# scs.net
KiCad netlist of a schematic drawn in EAGLE
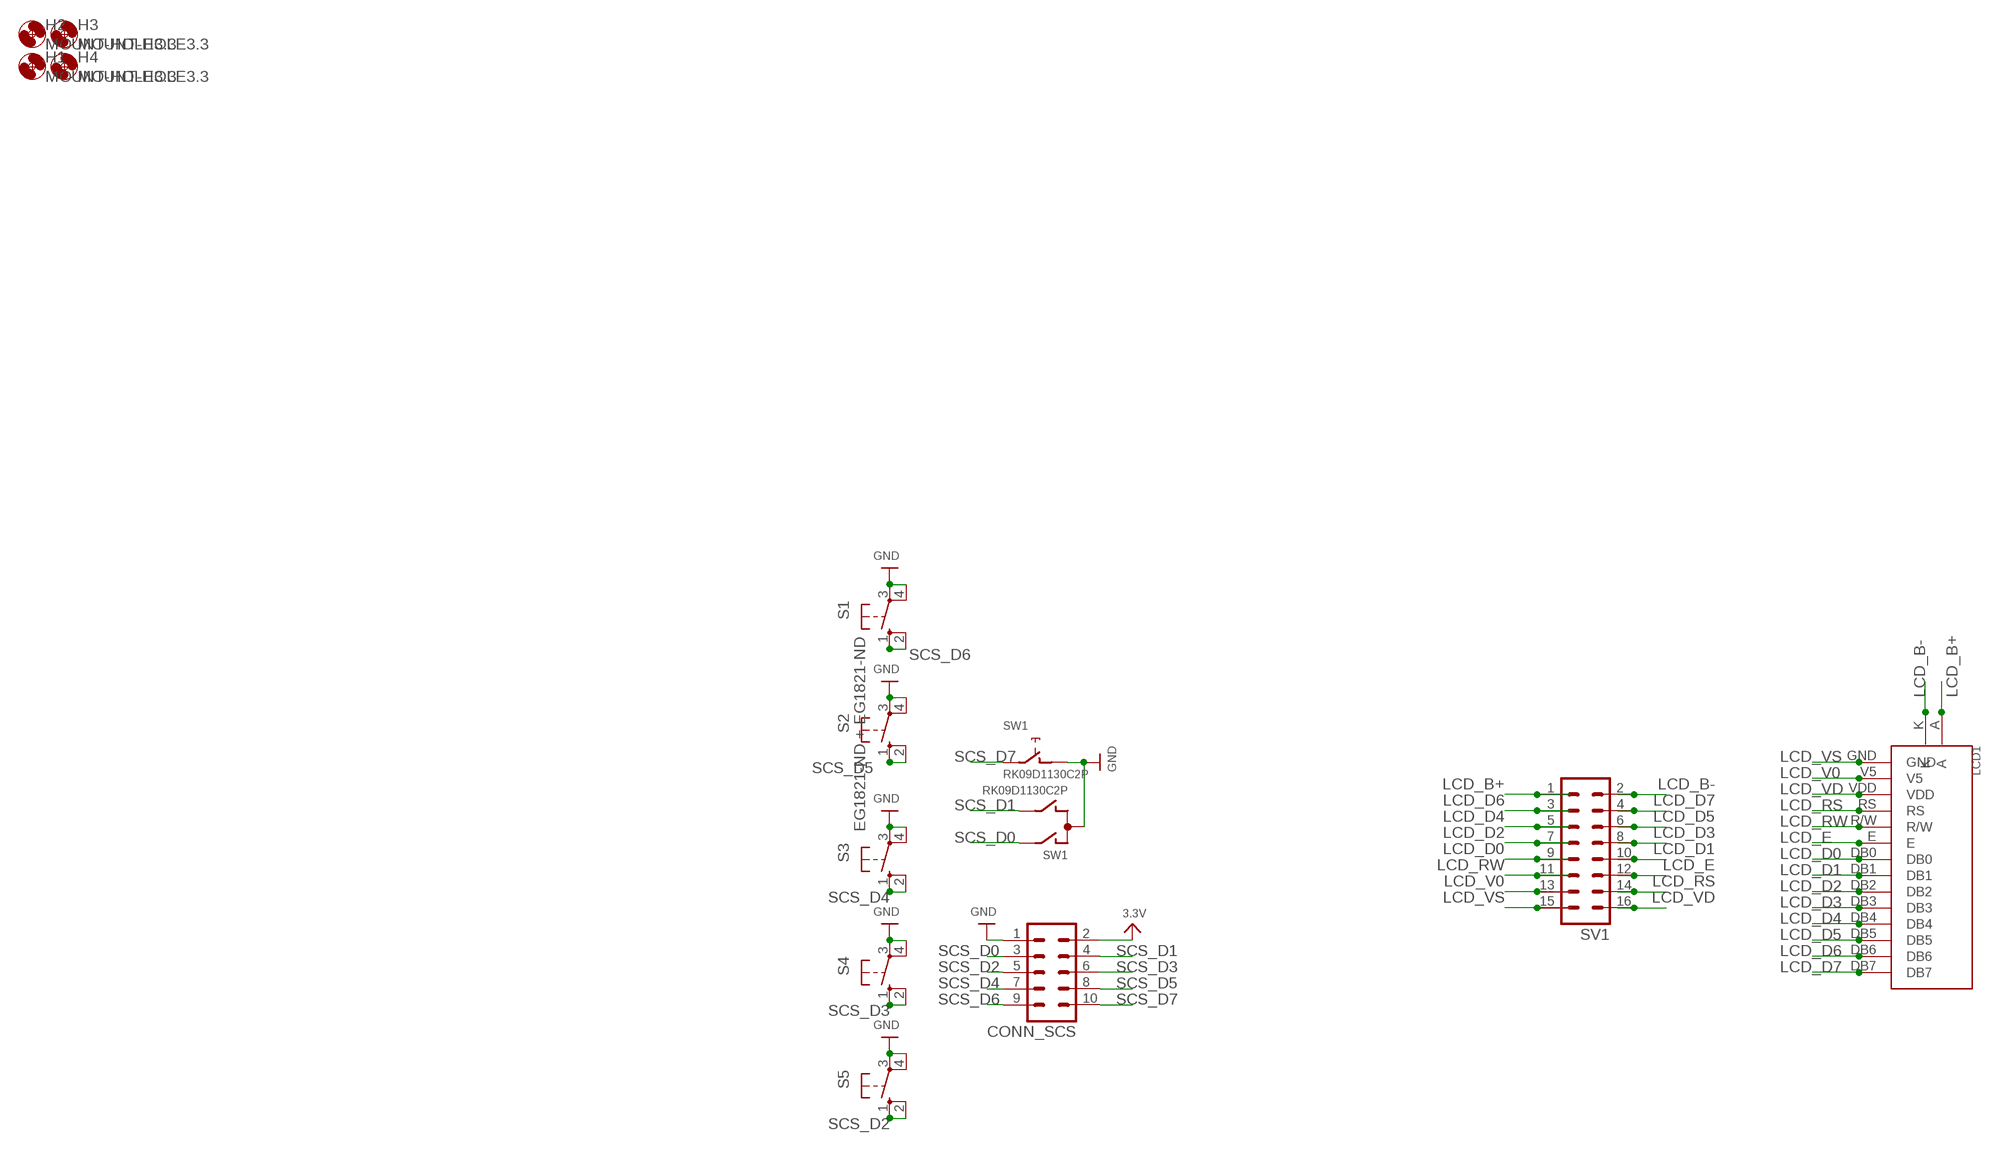
[diagram p0: schematic, sheet 1]

(export (version "E")
  (design (tool "Eeschema 10.0.6"))
  (components
    (comp (ref "CONN_SCS")
      (value "ML10")
      (footprint "eagle-import:ML10")
      (libsource (lib "eagle-import") (part "ML10"))
    )
    (comp (ref "H1")
      (value "MOUNT-HOLE3.3")
      (footprint "eagle-import:3,3")
      (libsource (lib "eagle-import") (part "MOUNT-HOLE3.3"))
    )
    (comp (ref "H2")
      (value "MOUNT-HOLE3.3")
      (footprint "eagle-import:3,3")
      (libsource (lib "eagle-import") (part "MOUNT-HOLE3.3"))
    )
    (comp (ref "H3")
      (value "MOUNT-HOLE3.3")
      (footprint "eagle-import:3,3")
      (libsource (lib "eagle-import") (part "MOUNT-HOLE3.3"))
    )
    (comp (ref "H4")
      (value "MOUNT-HOLE3.3")
      (footprint "eagle-import:3,3")
      (libsource (lib "eagle-import") (part "MOUNT-HOLE3.3"))
    )
    (comp (ref "LCD1")
      (value "NHD-C0220AA-FSW-FTW")
      (footprint "eagle-import:NHD-C0220AA-FSW-FTW")
      (libsource (lib "eagle-import") (part "NHD-C0220AA-FSW-FTW"))
    )
    (comp (ref "S1")
      (value "EG1821-ND + EG1821-ND")
      (footprint "eagle-import:B3F-40XX")
      (libsource (lib "eagle-import") (part "40-XX"))
    )
    (comp (ref "S2")
      (value "40-XX")
      (footprint "eagle-import:B3F-40XX")
      (libsource (lib "eagle-import") (part "40-XX"))
    )
    (comp (ref "S3")
      (value "40-XX")
      (footprint "eagle-import:B3F-40XX")
      (libsource (lib "eagle-import") (part "40-XX"))
    )
    (comp (ref "S4")
      (value "40-XX")
      (footprint "eagle-import:B3F-40XX")
      (libsource (lib "eagle-import") (part "40-XX"))
    )
    (comp (ref "S5")
      (value "40-XX")
      (footprint "eagle-import:B3F-40XX")
      (libsource (lib "eagle-import") (part "40-XX"))
    )
    (comp (ref "SV1")
      (value "ML16")
      (footprint "eagle-import:ML16")
      (libsource (lib "eagle-import") (part "ML16"))
    )
    (comp (ref "SW1")
      (value "RK09D1130C2P")
      (footprint "eagle-import:ALPS_EC12E_SW")
      (libsource (lib "eagle-import") (part "EC12E_SW"))
    )
  )
  (nets
    (net (code "1") (name "/LCD_B+") (class "Default")
      (node (ref "LCD1") (pin "A") (pinfunction "A_A") (pintype "bidirectional"))
      (node (ref "SV1") (pin "1") (pinfunction "1_1") (pintype "passive"))
    )
    (net (code "2") (name "/LCD_B-") (class "Default")
      (node (ref "LCD1") (pin "K") (pinfunction "K_K") (pintype "bidirectional"))
      (node (ref "SV1") (pin "2") (pinfunction "2_2") (pintype "passive"))
    )
    (net (code "3") (name "/LCD_D0") (class "Default")
      (node (ref "LCD1") (pin "DB0") (pinfunction "DB0_DB0") (pintype "bidirectional"))
      (node (ref "SV1") (pin "9") (pinfunction "9_9") (pintype "passive"))
    )
    (net (code "4") (name "/LCD_D1") (class "Default")
      (node (ref "LCD1") (pin "DB1") (pinfunction "DB1_DB1") (pintype "bidirectional"))
      (node (ref "SV1") (pin "10") (pinfunction "10_10") (pintype "passive"))
    )
    (net (code "5") (name "/LCD_D2") (class "Default")
      (node (ref "LCD1") (pin "DB2") (pinfunction "DB2_DB2") (pintype "bidirectional"))
      (node (ref "SV1") (pin "7") (pinfunction "7_7") (pintype "passive"))
    )
    (net (code "6") (name "/LCD_D3") (class "Default")
      (node (ref "LCD1") (pin "DB3") (pinfunction "DB3_DB3") (pintype "bidirectional"))
      (node (ref "SV1") (pin "8") (pinfunction "8_8") (pintype "passive"))
    )
    (net (code "7") (name "/LCD_D4") (class "Default")
      (node (ref "LCD1") (pin "DB4") (pinfunction "DB4_DB4") (pintype "bidirectional"))
      (node (ref "SV1") (pin "5") (pinfunction "5_5") (pintype "passive"))
    )
    (net (code "8") (name "/LCD_D5") (class "Default")
      (node (ref "LCD1") (pin "DB5") (pinfunction "DB5_DB5") (pintype "bidirectional"))
      (node (ref "SV1") (pin "6") (pinfunction "6_6") (pintype "passive"))
    )
    (net (code "9") (name "/LCD_D6") (class "Default")
      (node (ref "LCD1") (pin "DB6") (pinfunction "DB6_DB6") (pintype "bidirectional"))
      (node (ref "SV1") (pin "3") (pinfunction "3_3") (pintype "passive"))
    )
    (net (code "10") (name "/LCD_D7") (class "Default")
      (node (ref "LCD1") (pin "DB7") (pinfunction "DB7_DB7") (pintype "bidirectional"))
      (node (ref "SV1") (pin "4") (pinfunction "4_4") (pintype "passive"))
    )
    (net (code "11") (name "/LCD_E") (class "Default")
      (node (ref "LCD1") (pin "E") (pinfunction "E_E") (pintype "bidirectional"))
      (node (ref "SV1") (pin "12") (pinfunction "12_12") (pintype "passive"))
    )
    (net (code "12") (name "/LCD_RS") (class "Default")
      (node (ref "LCD1") (pin "RS") (pinfunction "RS_RS") (pintype "bidirectional"))
      (node (ref "SV1") (pin "14") (pinfunction "14_14") (pintype "passive"))
    )
    (net (code "13") (name "/LCD_RW") (class "Default")
      (node (ref "LCD1") (pin "R/W") (pinfunction "R/W_R/W") (pintype "bidirectional"))
      (node (ref "SV1") (pin "11") (pinfunction "11_11") (pintype "passive"))
    )
    (net (code "14") (name "/LCD_V0") (class "Default")
      (node (ref "LCD1") (pin "V5") (pinfunction "V5_V5") (pintype "bidirectional"))
      (node (ref "SV1") (pin "13") (pinfunction "13_13") (pintype "passive"))
    )
    (net (code "15") (name "/LCD_VD") (class "Default")
      (node (ref "LCD1") (pin "VDD") (pinfunction "VDD_VDD") (pintype "bidirectional"))
      (node (ref "SV1") (pin "16") (pinfunction "16_16") (pintype "passive"))
    )
    (net (code "16") (name "/LCD_VS") (class "Default")
      (node (ref "LCD1") (pin "GND") (pinfunction "GND_GND") (pintype "bidirectional"))
      (node (ref "SV1") (pin "15") (pinfunction "15_15") (pintype "passive"))
    )
    (net (code "17") (name "/SCS_D0") (class "Default")
      (node (ref "CONN_SCS") (pin "3") (pinfunction "3_3") (pintype "passive"))
      (node (ref "SW1") (pin "A") (pinfunction "A_A") (pintype "passive"))
    )
    (net (code "18") (name "/SCS_D1") (class "Default")
      (node (ref "CONN_SCS") (pin "4") (pinfunction "4_4") (pintype "passive"))
      (node (ref "SW1") (pin "B") (pinfunction "B_B") (pintype "passive"))
    )
    (net (code "19") (name "/SCS_D2") (class "Default")
      (node (ref "CONN_SCS") (pin "5") (pinfunction "5_5") (pintype "passive"))
      (node (ref "S5") (pin "1") (pinfunction "S_1") (pintype "passive"))
      (node (ref "S5") (pin "2") (pinfunction "S1_2") (pintype "passive"))
    )
    (net (code "20") (name "/SCS_D3") (class "Default")
      (node (ref "CONN_SCS") (pin "6") (pinfunction "6_6") (pintype "passive"))
      (node (ref "S4") (pin "1") (pinfunction "S_1") (pintype "passive"))
      (node (ref "S4") (pin "2") (pinfunction "S1_2") (pintype "passive"))
    )
    (net (code "21") (name "/SCS_D4") (class "Default")
      (node (ref "CONN_SCS") (pin "7") (pinfunction "7_7") (pintype "passive"))
      (node (ref "S3") (pin "1") (pinfunction "S_1") (pintype "passive"))
      (node (ref "S3") (pin "2") (pinfunction "S1_2") (pintype "passive"))
    )
    (net (code "22") (name "/SCS_D5") (class "Default")
      (node (ref "CONN_SCS") (pin "8") (pinfunction "8_8") (pintype "passive"))
      (node (ref "S2") (pin "1") (pinfunction "S_1") (pintype "passive"))
      (node (ref "S2") (pin "2") (pinfunction "S1_2") (pintype "passive"))
    )
    (net (code "23") (name "/SCS_D6") (class "Default")
      (node (ref "CONN_SCS") (pin "9") (pinfunction "9_9") (pintype "passive"))
      (node (ref "S1") (pin "1") (pinfunction "S_1") (pintype "passive"))
      (node (ref "S1") (pin "2") (pinfunction "S1_2") (pintype "passive"))
    )
    (net (code "24") (name "/SCS_D7") (class "Default")
      (node (ref "CONN_SCS") (pin "10") (pinfunction "10_10") (pintype "passive"))
      (node (ref "SW1") (pin "E") (pinfunction "2_E") (pintype "passive"))
    )
    (net (code "25") (name "3.3V") (class "Default")
      (node (ref "CONN_SCS") (pin "2") (pinfunction "2_2") (pintype "passive"))
    )
    (net (code "26") (name "GND") (class "Default")
      (node (ref "CONN_SCS") (pin "1") (pinfunction "1_1") (pintype "passive"))
      (node (ref "S1") (pin "3") (pinfunction "P_3") (pintype "passive"))
      (node (ref "S1") (pin "4") (pinfunction "P1_4") (pintype "passive"))
      (node (ref "S2") (pin "3") (pinfunction "P_3") (pintype "passive"))
      (node (ref "S2") (pin "4") (pinfunction "P1_4") (pintype "passive"))
      (node (ref "S3") (pin "3") (pinfunction "P_3") (pintype "passive"))
      (node (ref "S3") (pin "4") (pinfunction "P1_4") (pintype "passive"))
      (node (ref "S4") (pin "3") (pinfunction "P_3") (pintype "passive"))
      (node (ref "S4") (pin "4") (pinfunction "P1_4") (pintype "passive"))
      (node (ref "S5") (pin "3") (pinfunction "P_3") (pintype "passive"))
      (node (ref "S5") (pin "4") (pinfunction "P1_4") (pintype "passive"))
      (node (ref "SW1") (pin "C") (pinfunction "C_C") (pintype "passive"))
      (node (ref "SW1") (pin "D") (pinfunction "1_D") (pintype "passive"))
    )
  )
)
